# Rsim_V1_0.net
KiCad netlist of a schematic drawn in Altium Designer
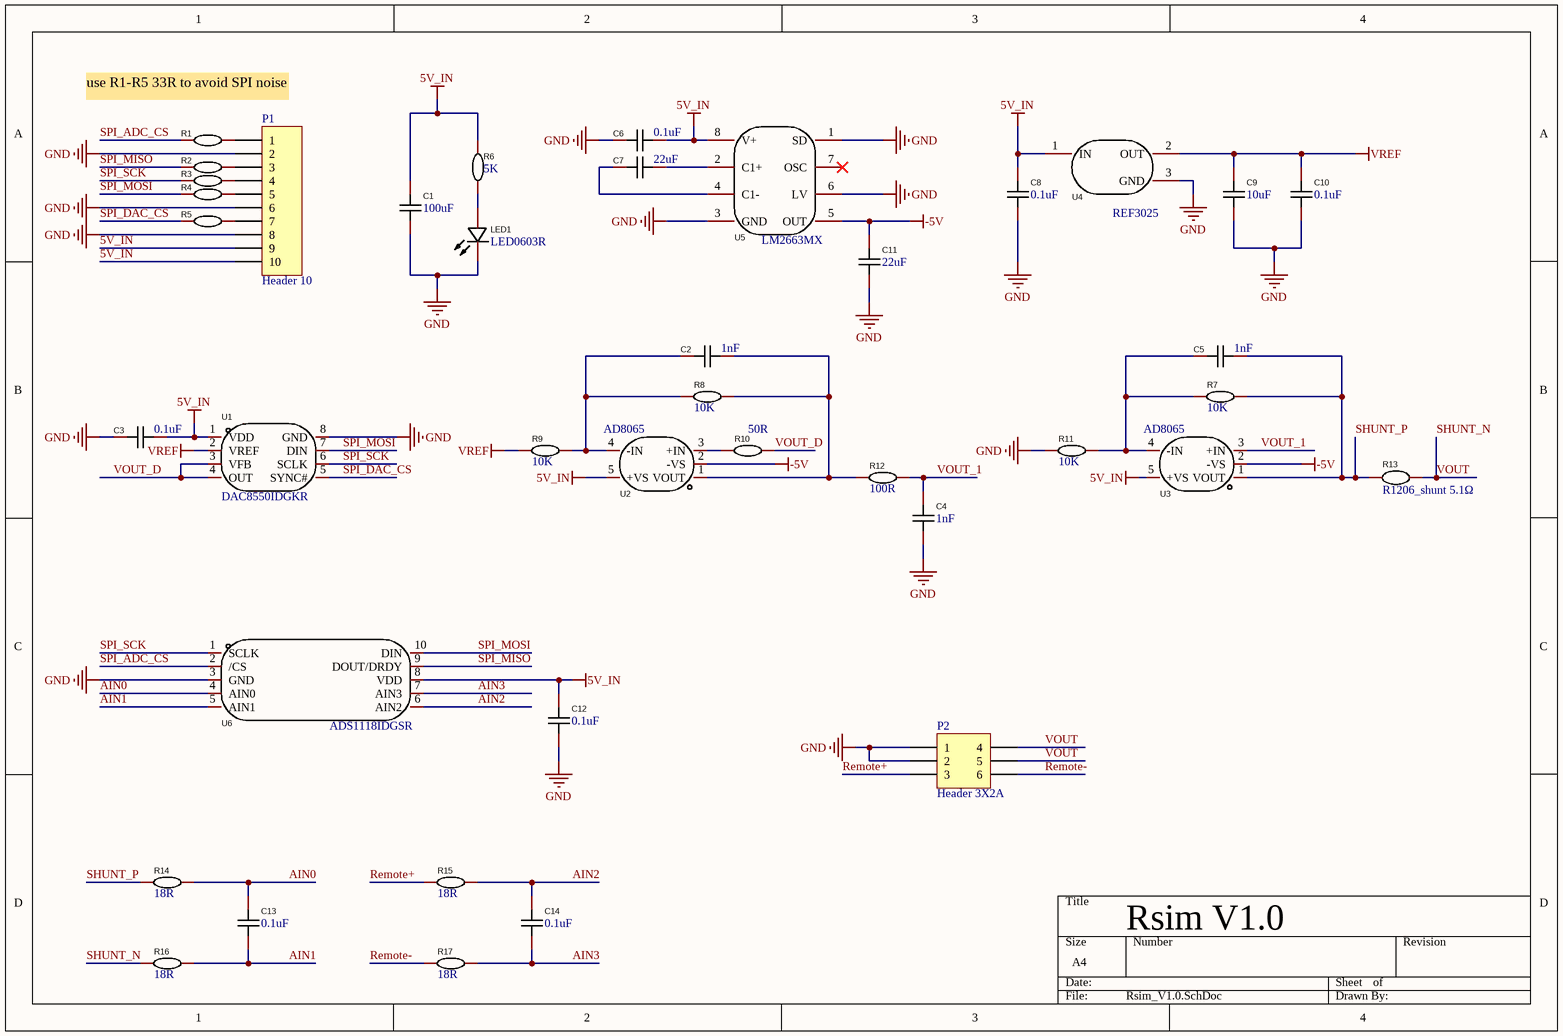
[diagram p0: Rsim_V1.0.SchDoc]

(export (version "E")
  (design (tool "Eeschema 10.0.6"))
  (components
    (comp (ref "C1")
      (value "100uF")
      (footprint "C0603")
      (fields (field (name "MANUFACTURER") "FH(风华)") (field (name "MANUFACTURER PART") "0603DS475K160NT"))
      (libsource (lib "20240501") (part "0603CAP"))
    )
    (comp (ref "C2")
      (value "1nF")
      (footprint "C0603")
      (fields (field (name "MANUFACTURER") "FH(风华)") (field (name "MANUFACTURER PART") "0603DS475K160NT"))
      (libsource (lib "20240501") (part "0603CAP"))
    )
    (comp (ref "C3")
      (value "0.1uF")
      (footprint "C0603")
      (fields (field (name "MANUFACTURER") "FH(风华)") (field (name "MANUFACTURER PART") "0603DS475K160NT"))
      (libsource (lib "20240501") (part "0603CAP"))
    )
    (comp (ref "C4")
      (value "1nF")
      (footprint "C0603")
      (fields (field (name "MANUFACTURER") "FH(风华)") (field (name "MANUFACTURER PART") "0603DS475K160NT"))
      (libsource (lib "20240501") (part "0603CAP"))
    )
    (comp (ref "C5")
      (value "1nF")
      (footprint "C0603")
      (fields (field (name "MANUFACTURER") "FH(风华)") (field (name "MANUFACTURER PART") "0603DS475K160NT"))
      (libsource (lib "20240501") (part "0603CAP"))
    )
    (comp (ref "C6")
      (value "0.1uF")
      (footprint "C0603")
      (fields (field (name "MANUFACTURER") "FH(风华)") (field (name "MANUFACTURER PART") "0603DS475K160NT"))
      (libsource (lib "20240501") (part "0603CAP"))
    )
    (comp (ref "C7")
      (value "22uF")
      (footprint "C0603")
      (fields (field (name "MANUFACTURER") "FH(风华)") (field (name "MANUFACTURER PART") "0603DS475K160NT"))
      (libsource (lib "20240501") (part "0603CAP"))
    )
    (comp (ref "C8")
      (value "0.1uF")
      (footprint "C0603")
      (fields (field (name "MANUFACTURER") "FH(风华)") (field (name "MANUFACTURER PART") "0603DS475K160NT"))
      (libsource (lib "20240501") (part "0603CAP"))
    )
    (comp (ref "C9")
      (value "10uF")
      (footprint "C0603")
      (fields (field (name "MANUFACTURER") "FH(风华)") (field (name "MANUFACTURER PART") "0603DS475K160NT"))
      (libsource (lib "20240501") (part "0603CAP"))
    )
    (comp (ref "C10")
      (value "0.1uF")
      (footprint "C0603")
      (fields (field (name "MANUFACTURER") "FH(风华)") (field (name "MANUFACTURER PART") "0603DS475K160NT"))
      (libsource (lib "20240501") (part "0603CAP"))
    )
    (comp (ref "C11")
      (value "22uF")
      (footprint "C0603")
      (fields (field (name "MANUFACTURER") "FH(风华)") (field (name "MANUFACTURER PART") "0603DS475K160NT"))
      (libsource (lib "20240501") (part "0603CAP"))
    )
    (comp (ref "C12")
      (value "0.1uF")
      (footprint "C0603")
      (fields (field (name "MANUFACTURER") "FH(风华)") (field (name "MANUFACTURER PART") "0603DS475K160NT"))
      (libsource (lib "20240501") (part "0603CAP"))
    )
    (comp (ref "C13")
      (value "0.1uF")
      (footprint "C0603")
      (fields (field (name "MANUFACTURER") "FH(风华)") (field (name "MANUFACTURER PART") "0603DS475K160NT"))
      (libsource (lib "20240501") (part "0603CAP"))
    )
    (comp (ref "C14")
      (value "0.1uF")
      (footprint "C0603")
      (fields (field (name "MANUFACTURER") "FH(风华)") (field (name "MANUFACTURER PART") "0603DS475K160NT"))
      (libsource (lib "20240501") (part "0603CAP"))
    )
    (comp (ref "LED1")
      (value "LED0603R")
      (footprint "LED0603-R-RD")
      (fields (field (name "MANUFACTURER") "yongyu(永裕光电)") (field (name "MANUFACTURER PART") "SZYY0603R"))
      (libsource (lib "20240501") (part "LED0603R"))
    )
    (comp (ref "P1")
      (value "Header 10")
      (footprint "HDR1X10")
      (description "Header, 10-Pin")
      (fields (field (name "PUBLISHER") "Altium Limited"))
      (libsource (lib "Miscellaneous Connectors") (part "Header 10"))
    )
    (comp (ref "P2")
      (value "Header 3X2A")
      (footprint "HDR2X3_CEN")
      (description "Header, 3-Pin, Dual row")
      (fields (field (name "PUBLISHER") "Altium Limited"))
      (libsource (lib "Miscellaneous Connectors") (part "Header 3X2A"))
    )
    (comp (ref "R1")
      (value "33R")
      (footprint "R0603")
      (fields
        (field (name "MANUFACTURER") "UNI-ROYAL(厚声)")
        (field (name "MANUFACTURER PART") "0603WAF1002T5E")
        (field (name "TOLERANCE") "±1%")
      )
      (libsource (lib "20240501") (part "0603RES"))
    )
    (comp (ref "R2")
      (value "33R")
      (footprint "R0603")
      (fields
        (field (name "MANUFACTURER") "UNI-ROYAL(厚声)")
        (field (name "MANUFACTURER PART") "0603WAF1002T5E")
        (field (name "TOLERANCE") "±1%")
      )
      (libsource (lib "20240501") (part "0603RES"))
    )
    (comp (ref "R3")
      (value "33R")
      (footprint "R0603")
      (fields
        (field (name "MANUFACTURER") "UNI-ROYAL(厚声)")
        (field (name "MANUFACTURER PART") "0603WAF1002T5E")
        (field (name "TOLERANCE") "±1%")
      )
      (libsource (lib "20240501") (part "0603RES"))
    )
    (comp (ref "R4")
      (value "33R")
      (footprint "R0603")
      (fields
        (field (name "MANUFACTURER") "UNI-ROYAL(厚声)")
        (field (name "MANUFACTURER PART") "0603WAF1002T5E")
        (field (name "TOLERANCE") "±1%")
      )
      (libsource (lib "20240501") (part "0603RES"))
    )
    (comp (ref "R5")
      (value "33R")
      (footprint "R0603")
      (fields
        (field (name "MANUFACTURER") "UNI-ROYAL(厚声)")
        (field (name "MANUFACTURER PART") "0603WAF1002T5E")
        (field (name "TOLERANCE") "±1%")
      )
      (libsource (lib "20240501") (part "0603RES"))
    )
    (comp (ref "R6")
      (value "5K")
      (footprint "R0603")
      (fields
        (field (name "MANUFACTURER") "UNI-ROYAL(厚声)")
        (field (name "MANUFACTURER PART") "0603WAF1002T5E")
        (field (name "TOLERANCE") "±1%")
      )
      (libsource (lib "20240501") (part "0603RES"))
    )
    (comp (ref "R7")
      (value "10K")
      (footprint "R0603")
      (fields
        (field (name "MANUFACTURER") "UNI-ROYAL(厚声)")
        (field (name "MANUFACTURER PART") "0603WAF1002T5E")
        (field (name "TOLERANCE") "±1%")
      )
      (libsource (lib "20240501") (part "0603RES"))
    )
    (comp (ref "R8")
      (value "10K")
      (footprint "R0603")
      (fields
        (field (name "MANUFACTURER") "UNI-ROYAL(厚声)")
        (field (name "MANUFACTURER PART") "0603WAF1002T5E")
        (field (name "TOLERANCE") "±1%")
      )
      (libsource (lib "20240501") (part "0603RES"))
    )
    (comp (ref "R9")
      (value "10K")
      (footprint "R0603")
      (fields
        (field (name "MANUFACTURER") "UNI-ROYAL(厚声)")
        (field (name "MANUFACTURER PART") "0603WAF1002T5E")
        (field (name "TOLERANCE") "±1%")
      )
      (libsource (lib "20240501") (part "0603RES"))
    )
    (comp (ref "R10")
      (value "50R")
      (footprint "R0603")
      (fields
        (field (name "MANUFACTURER") "UNI-ROYAL(厚声)")
        (field (name "MANUFACTURER PART") "0603WAF1002T5E")
        (field (name "TOLERANCE") "±1%")
      )
      (libsource (lib "20240501") (part "0603RES"))
    )
    (comp (ref "R11")
      (value "10K")
      (footprint "R0603")
      (fields
        (field (name "MANUFACTURER") "UNI-ROYAL(厚声)")
        (field (name "MANUFACTURER PART") "0603WAF1002T5E")
        (field (name "TOLERANCE") "±1%")
      )
      (libsource (lib "20240501") (part "0603RES"))
    )
    (comp (ref "R12")
      (value "100R")
      (footprint "R0603")
      (fields
        (field (name "MANUFACTURER") "UNI-ROYAL(厚声)")
        (field (name "MANUFACTURER PART") "0603WAF1002T5E")
        (field (name "TOLERANCE") "±1%")
      )
      (libsource (lib "20240501") (part "0603RES"))
    )
    (comp (ref "R13")
      (value "R1206_shunt 5.1Ω")
      (footprint "R1206")
      (fields
        (field (name "MANUFACTURER") "Milliohm(毫欧)")
        (field (name "MANUFACTURER PART") "HoLLR1206-1W-5mR-1%")
        (field (name "TOLERANCE") "±1%")
      )
      (libsource (lib "20240501") (part "R1206_shunt"))
    )
    (comp (ref "R14")
      (value "18R")
      (footprint "R0603")
      (fields
        (field (name "MANUFACTURER") "UNI-ROYAL(厚声)")
        (field (name "MANUFACTURER PART") "0603WAF1002T5E")
        (field (name "TOLERANCE") "±1%")
      )
      (libsource (lib "20240501") (part "0603RES"))
    )
    (comp (ref "R15")
      (value "18R")
      (footprint "R0603")
      (fields
        (field (name "MANUFACTURER") "UNI-ROYAL(厚声)")
        (field (name "MANUFACTURER PART") "0603WAF1002T5E")
        (field (name "TOLERANCE") "±1%")
      )
      (libsource (lib "20240501") (part "0603RES"))
    )
    (comp (ref "R16")
      (value "18R")
      (footprint "R0603")
      (fields
        (field (name "MANUFACTURER") "UNI-ROYAL(厚声)")
        (field (name "MANUFACTURER PART") "0603WAF1002T5E")
        (field (name "TOLERANCE") "±1%")
      )
      (libsource (lib "20240501") (part "0603RES"))
    )
    (comp (ref "R17")
      (value "18R")
      (footprint "R0603")
      (fields
        (field (name "MANUFACTURER") "UNI-ROYAL(厚声)")
        (field (name "MANUFACTURER PART") "0603WAF1002T5E")
        (field (name "TOLERANCE") "±1%")
      )
      (libsource (lib "20240501") (part "0603RES"))
    )
    (comp (ref "U1")
      (value "DAC8550IDGKR")
      (footprint "VSSOP-8_L3.0-W3.0-P0.65-LS5.0-BL")
      (fields (field (name "MANUFACTURER") "TI(德州仪器)"))
      (libsource (lib "20240501") (part "DAC8550IDGKR"))
    )
    (comp (ref "U2")
      (value "AD8065")
      (footprint "SOT-23-5_L3.0-W1.7-P0.95-LS2.8-BR")
      (fields (field (name "MANUFACTURER") "ADI(亚德诺)") (field (name "MANUFACTURER PART") "AD8065ARTZ-REEL7"))
      (libsource (lib "20240501") (part "AD8065ARTZ-REEL7"))
    )
    (comp (ref "U3")
      (value "AD8065")
      (footprint "SOT-23-5_L3.0-W1.7-P0.95-LS2.8-BR")
      (fields (field (name "MANUFACTURER") "ADI(亚德诺)") (field (name "MANUFACTURER PART") "AD8065ARTZ-REEL7"))
      (libsource (lib "20240501") (part "AD8065ARTZ-REEL7"))
    )
    (comp (ref "U4")
      (value "REF3025")
      (footprint "SOT-23-3_L2.9-W1.6-P1.90-LS2.8-BR")
      (fields
        (field (name "MANUFACTURER") "TI(德州仪器)")
        (field (name "MANUFACTURER PART") "REF3025AIDBZR")
        (field (name "TOLERANCE") "±0.2%")
      )
      (libsource (lib "20240501") (part "REF3025AIDBZR"))
    )
    (comp (ref "U5")
      (value "LM2663MX")
      (footprint "SOIC-8_L4.9-W3.9-P1.27-LS6.0-BL")
      (fields (field (name "MANUFACTURER") "TI(德州仪器)") (field (name "MANUFACTURER PART") "LM2663MX/NOPB"))
      (libsource (lib "20240501") (part "LM2663MX/NOPB"))
    )
    (comp (ref "U6")
      (value "ADS1118IDGSR")
      (footprint "VSSOP-10_L3.0-W3.0-P0.50-LS4.9-BL")
      (fields (field (name "MANUFACTURER") "TI(德州仪器)"))
      (libsource (lib "20240501") (part "ADS1118IDGSR"))
    )
  )
  (nets
    (net (code "1") (name "-5V") (class "Default")
      (node (ref "C11") (pin "2") (pinfunction "2_2") (pintype "passive"))
      (node (ref "U2") (pin "2") (pinfunction "-VS_2") (pintype "passive"))
      (node (ref "U3") (pin "2") (pinfunction "-VS_2") (pintype "passive"))
      (node (ref "U5") (pin "5") (pinfunction "OUT_5") (pintype "passive"))
    )
    (net (code "2") (name "/AIN0") (class "Default")
      (node (ref "C13") (pin "1") (pinfunction "1_1") (pintype "passive"))
      (node (ref "R14") (pin "1") (pinfunction "1_1") (pintype "passive"))
      (node (ref "U6") (pin "4") (pinfunction "AIN0_4") (pintype "passive"))
    )
    (net (code "3") (name "/AIN1") (class "Default")
      (node (ref "C13") (pin "2") (pinfunction "2_2") (pintype "passive"))
      (node (ref "R16") (pin "1") (pinfunction "1_1") (pintype "passive"))
      (node (ref "U6") (pin "5") (pinfunction "AIN1_5") (pintype "passive"))
    )
    (net (code "4") (name "/AIN2") (class "Default")
      (node (ref "C14") (pin "1") (pinfunction "1_1") (pintype "passive"))
      (node (ref "R15") (pin "1") (pinfunction "1_1") (pintype "passive"))
      (node (ref "U6") (pin "6") (pinfunction "AIN2_6") (pintype "passive"))
    )
    (net (code "5") (name "/AIN3") (class "Default")
      (node (ref "C14") (pin "2") (pinfunction "2_2") (pintype "passive"))
      (node (ref "R17") (pin "1") (pinfunction "1_1") (pintype "passive"))
      (node (ref "U6") (pin "7") (pinfunction "AIN3_7") (pintype "passive"))
    )
    (net (code "6") (name "/Remote+") (class "Default")
      (node (ref "P2") (pin "3") (pinfunction "3_3") (pintype "passive"))
      (node (ref "R15") (pin "2") (pinfunction "2_2") (pintype "passive"))
    )
    (net (code "7") (name "/Remote-") (class "Default")
      (node (ref "P2") (pin "6") (pinfunction "6_6") (pintype "passive"))
      (node (ref "R17") (pin "2") (pinfunction "2_2") (pintype "passive"))
    )
    (net (code "8") (name "/SHUNT_N") (class "Default")
      (node (ref "P2") (pin "4") (pinfunction "4_4") (pintype "passive"))
      (node (ref "P2") (pin "5") (pinfunction "5_5") (pintype "passive"))
      (node (ref "R13") (pin "2") (pinfunction "2_2") (pintype "passive"))
      (node (ref "R16") (pin "2") (pinfunction "2_2") (pintype "passive"))
    )
    (net (code "9") (name "/SHUNT_P") (class "Default")
      (node (ref "C5") (pin "1") (pinfunction "1_1") (pintype "passive"))
      (node (ref "R13") (pin "1") (pinfunction "1_1") (pintype "passive"))
      (node (ref "R14") (pin "2") (pinfunction "2_2") (pintype "passive"))
      (node (ref "R7") (pin "1") (pinfunction "1_1") (pintype "passive"))
      (node (ref "U3") (pin "1") (pinfunction "VOUT_1") (pintype "passive"))
    )
    (net (code "10") (name "/SPI_ADC_CS") (class "Default")
      (node (ref "R1") (pin "1") (pinfunction "1_1") (pintype "passive"))
      (node (ref "U6") (pin "2") (pinfunction "/CS_2") (pintype "passive"))
    )
    (net (code "11") (name "/SPI_DAC_CS") (class "Default")
      (node (ref "R5") (pin "1") (pinfunction "1_1") (pintype "passive"))
      (node (ref "U1") (pin "5") (pinfunction "SYNC#_5") (pintype "passive"))
    )
    (net (code "12") (name "/SPI_MISO") (class "Default")
      (node (ref "R2") (pin "1") (pinfunction "1_1") (pintype "passive"))
      (node (ref "U6") (pin "9") (pinfunction "DOUT/DRDY_9") (pintype "passive"))
    )
    (net (code "13") (name "/SPI_MOSI") (class "Default")
      (node (ref "R4") (pin "1") (pinfunction "1_1") (pintype "passive"))
      (node (ref "U1") (pin "7") (pinfunction "DIN_7") (pintype "passive"))
      (node (ref "U6") (pin "10") (pinfunction "DIN_10") (pintype "passive"))
    )
    (net (code "14") (name "/SPI_SCK") (class "Default")
      (node (ref "R3") (pin "1") (pinfunction "1_1") (pintype "passive"))
      (node (ref "U1") (pin "6") (pinfunction "SCLK_6") (pintype "passive"))
      (node (ref "U6") (pin "1") (pinfunction "SCLK_1") (pintype "passive"))
    )
    (net (code "15") (name "/VOUT_1") (class "Default")
      (node (ref "C4") (pin "1") (pinfunction "1_1") (pintype "passive"))
      (node (ref "R12") (pin "1") (pinfunction "1_1") (pintype "passive"))
      (node (ref "U3") (pin "3") (pinfunction "+IN_3") (pintype "passive"))
    )
    (net (code "16") (name "/VOUT_D") (class "Default")
      (node (ref "R10") (pin "1") (pinfunction "1_1") (pintype "passive"))
      (node (ref "U1") (pin "3") (pinfunction "VFB_3") (pintype "passive"))
      (node (ref "U1") (pin "4") (pinfunction "OUT_4") (pintype "passive"))
    )
    (net (code "17") (name "5V_IN") (class "Default")
      (node (ref "C1") (pin "2") (pinfunction "2_2") (pintype "passive"))
      (node (ref "C12") (pin "1") (pinfunction "1_1") (pintype "passive"))
      (node (ref "C3") (pin "1") (pinfunction "1_1") (pintype "passive"))
      (node (ref "C6") (pin "1") (pinfunction "1_1") (pintype "passive"))
      (node (ref "C8") (pin "1") (pinfunction "1_1") (pintype "passive"))
      (node (ref "P1") (pin "10") (pinfunction "10_10") (pintype "passive"))
      (node (ref "P1") (pin "9") (pinfunction "9_9") (pintype "passive"))
      (node (ref "R6") (pin "2") (pinfunction "2_2") (pintype "passive"))
      (node (ref "U1") (pin "1") (pinfunction "VDD_1") (pintype "passive"))
      (node (ref "U2") (pin "5") (pinfunction "+VS_5") (pintype "passive"))
      (node (ref "U3") (pin "5") (pinfunction "+VS_5") (pintype "passive"))
      (node (ref "U4") (pin "1") (pinfunction "IN_1") (pintype "passive"))
      (node (ref "U5") (pin "8") (pinfunction "V+_8") (pintype "passive"))
      (node (ref "U6") (pin "8") (pinfunction "VDD_8") (pintype "passive"))
    )
    (net (code "18") (name "GND") (class "Default")
      (node (ref "C1") (pin "1") (pinfunction "1_1") (pintype "passive"))
      (node (ref "C10") (pin "2") (pinfunction "2_2") (pintype "passive"))
      (node (ref "C11") (pin "1") (pinfunction "1_1") (pintype "passive"))
      (node (ref "C12") (pin "2") (pinfunction "2_2") (pintype "passive"))
      (node (ref "C3") (pin "2") (pinfunction "2_2") (pintype "passive"))
      (node (ref "C4") (pin "2") (pinfunction "2_2") (pintype "passive"))
      (node (ref "C6") (pin "2") (pinfunction "2_2") (pintype "passive"))
      (node (ref "C8") (pin "2") (pinfunction "2_2") (pintype "passive"))
      (node (ref "C9") (pin "2") (pinfunction "2_2") (pintype "passive"))
      (node (ref "LED1") (pin "2") (pinfunction "-_2") (pintype "passive"))
      (node (ref "P1") (pin "2") (pinfunction "2_2") (pintype "passive"))
      (node (ref "P1") (pin "6") (pinfunction "6_6") (pintype "passive"))
      (node (ref "P1") (pin "8") (pinfunction "8_8") (pintype "passive"))
      (node (ref "P2") (pin "1") (pinfunction "1_1") (pintype "passive"))
      (node (ref "P2") (pin "2") (pinfunction "2_2") (pintype "passive"))
      (node (ref "R11") (pin "2") (pinfunction "2_2") (pintype "passive"))
      (node (ref "U1") (pin "8") (pinfunction "GND_8") (pintype "passive"))
      (node (ref "U4") (pin "3") (pinfunction "GND_3") (pintype "passive"))
      (node (ref "U5") (pin "1") (pinfunction "SD_1") (pintype "passive"))
      (node (ref "U5") (pin "3") (pinfunction "GND_3") (pintype "passive"))
      (node (ref "U5") (pin "6") (pinfunction "LV_6") (pintype "passive"))
      (node (ref "U6") (pin "3") (pinfunction "GND_3") (pintype "passive"))
    )
    (net (code "19") (name "Net-(LED1-+)") (class "Default")
      (node (ref "LED1") (pin "1") (pinfunction "+_1") (pintype "passive"))
      (node (ref "R6") (pin "1") (pinfunction "1_1") (pintype "passive"))
    )
    (net (code "20") (name "Net-(P1-Pad1)") (class "Default")
      (node (ref "P1") (pin "1") (pinfunction "1_1") (pintype "passive"))
      (node (ref "R1") (pin "2") (pinfunction "2_2") (pintype "passive"))
    )
    (net (code "21") (name "Net-(P1-Pad3)") (class "Default")
      (node (ref "P1") (pin "3") (pinfunction "3_3") (pintype "passive"))
      (node (ref "R2") (pin "2") (pinfunction "2_2") (pintype "passive"))
    )
    (net (code "22") (name "Net-(P1-Pad4)") (class "Default")
      (node (ref "P1") (pin "4") (pinfunction "4_4") (pintype "passive"))
      (node (ref "R3") (pin "2") (pinfunction "2_2") (pintype "passive"))
    )
    (net (code "23") (name "Net-(P1-Pad5)") (class "Default")
      (node (ref "P1") (pin "5") (pinfunction "5_5") (pintype "passive"))
      (node (ref "R4") (pin "2") (pinfunction "2_2") (pintype "passive"))
    )
    (net (code "24") (name "Net-(P1-Pad7)") (class "Default")
      (node (ref "P1") (pin "7") (pinfunction "7_7") (pintype "passive"))
      (node (ref "R5") (pin "2") (pinfunction "2_2") (pintype "passive"))
    )
    (net (code "25") (name "Net-(U2-+IN)") (class "Default")
      (node (ref "R10") (pin "2") (pinfunction "2_2") (pintype "passive"))
      (node (ref "U2") (pin "3") (pinfunction "+IN_3") (pintype "passive"))
    )
    (net (code "26") (name "Net-(U2--IN)") (class "Default")
      (node (ref "C2") (pin "2") (pinfunction "2_2") (pintype "passive"))
      (node (ref "R8") (pin "2") (pinfunction "2_2") (pintype "passive"))
      (node (ref "R9") (pin "1") (pinfunction "1_1") (pintype "passive"))
      (node (ref "U2") (pin "4") (pinfunction "-IN_4") (pintype "passive"))
    )
    (net (code "27") (name "Net-(U2-VOUT)") (class "Default")
      (node (ref "C2") (pin "1") (pinfunction "1_1") (pintype "passive"))
      (node (ref "R12") (pin "2") (pinfunction "2_2") (pintype "passive"))
      (node (ref "R8") (pin "1") (pinfunction "1_1") (pintype "passive"))
      (node (ref "U2") (pin "1") (pinfunction "VOUT_1") (pintype "passive"))
    )
    (net (code "28") (name "Net-(U3--IN)") (class "Default")
      (node (ref "C5") (pin "2") (pinfunction "2_2") (pintype "passive"))
      (node (ref "R11") (pin "1") (pinfunction "1_1") (pintype "passive"))
      (node (ref "R7") (pin "2") (pinfunction "2_2") (pintype "passive"))
      (node (ref "U3") (pin "4") (pinfunction "-IN_4") (pintype "passive"))
    )
    (net (code "29") (name "Net-(U5-C1+)") (class "Default")
      (node (ref "C7") (pin "1") (pinfunction "1_1") (pintype "passive"))
      (node (ref "U5") (pin "2") (pinfunction "C1+_2") (pintype "passive"))
    )
    (net (code "30") (name "Net-(U5-C1-)") (class "Default")
      (node (ref "C7") (pin "2") (pinfunction "2_2") (pintype "passive"))
      (node (ref "U5") (pin "4") (pinfunction "C1-_4") (pintype "passive"))
    )
    (net (code "31") (name "VREF") (class "Default")
      (node (ref "C10") (pin "1") (pinfunction "1_1") (pintype "passive"))
      (node (ref "C9") (pin "1") (pinfunction "1_1") (pintype "passive"))
      (node (ref "R9") (pin "2") (pinfunction "2_2") (pintype "passive"))
      (node (ref "U1") (pin "2") (pinfunction "VREF_2") (pintype "passive"))
      (node (ref "U4") (pin "2") (pinfunction "OUT_2") (pintype "passive"))
    )
    (net (code "32") (name "unconnected-(U5-OSC-Pad7)") (class "Default")
      (node (ref "U5") (pin "7") (pinfunction "OSC_7") (pintype "passive+no_connect"))
    )
  )
)
